# MODI3.net
KiCad netlist of a schematic drawn in EAGLE
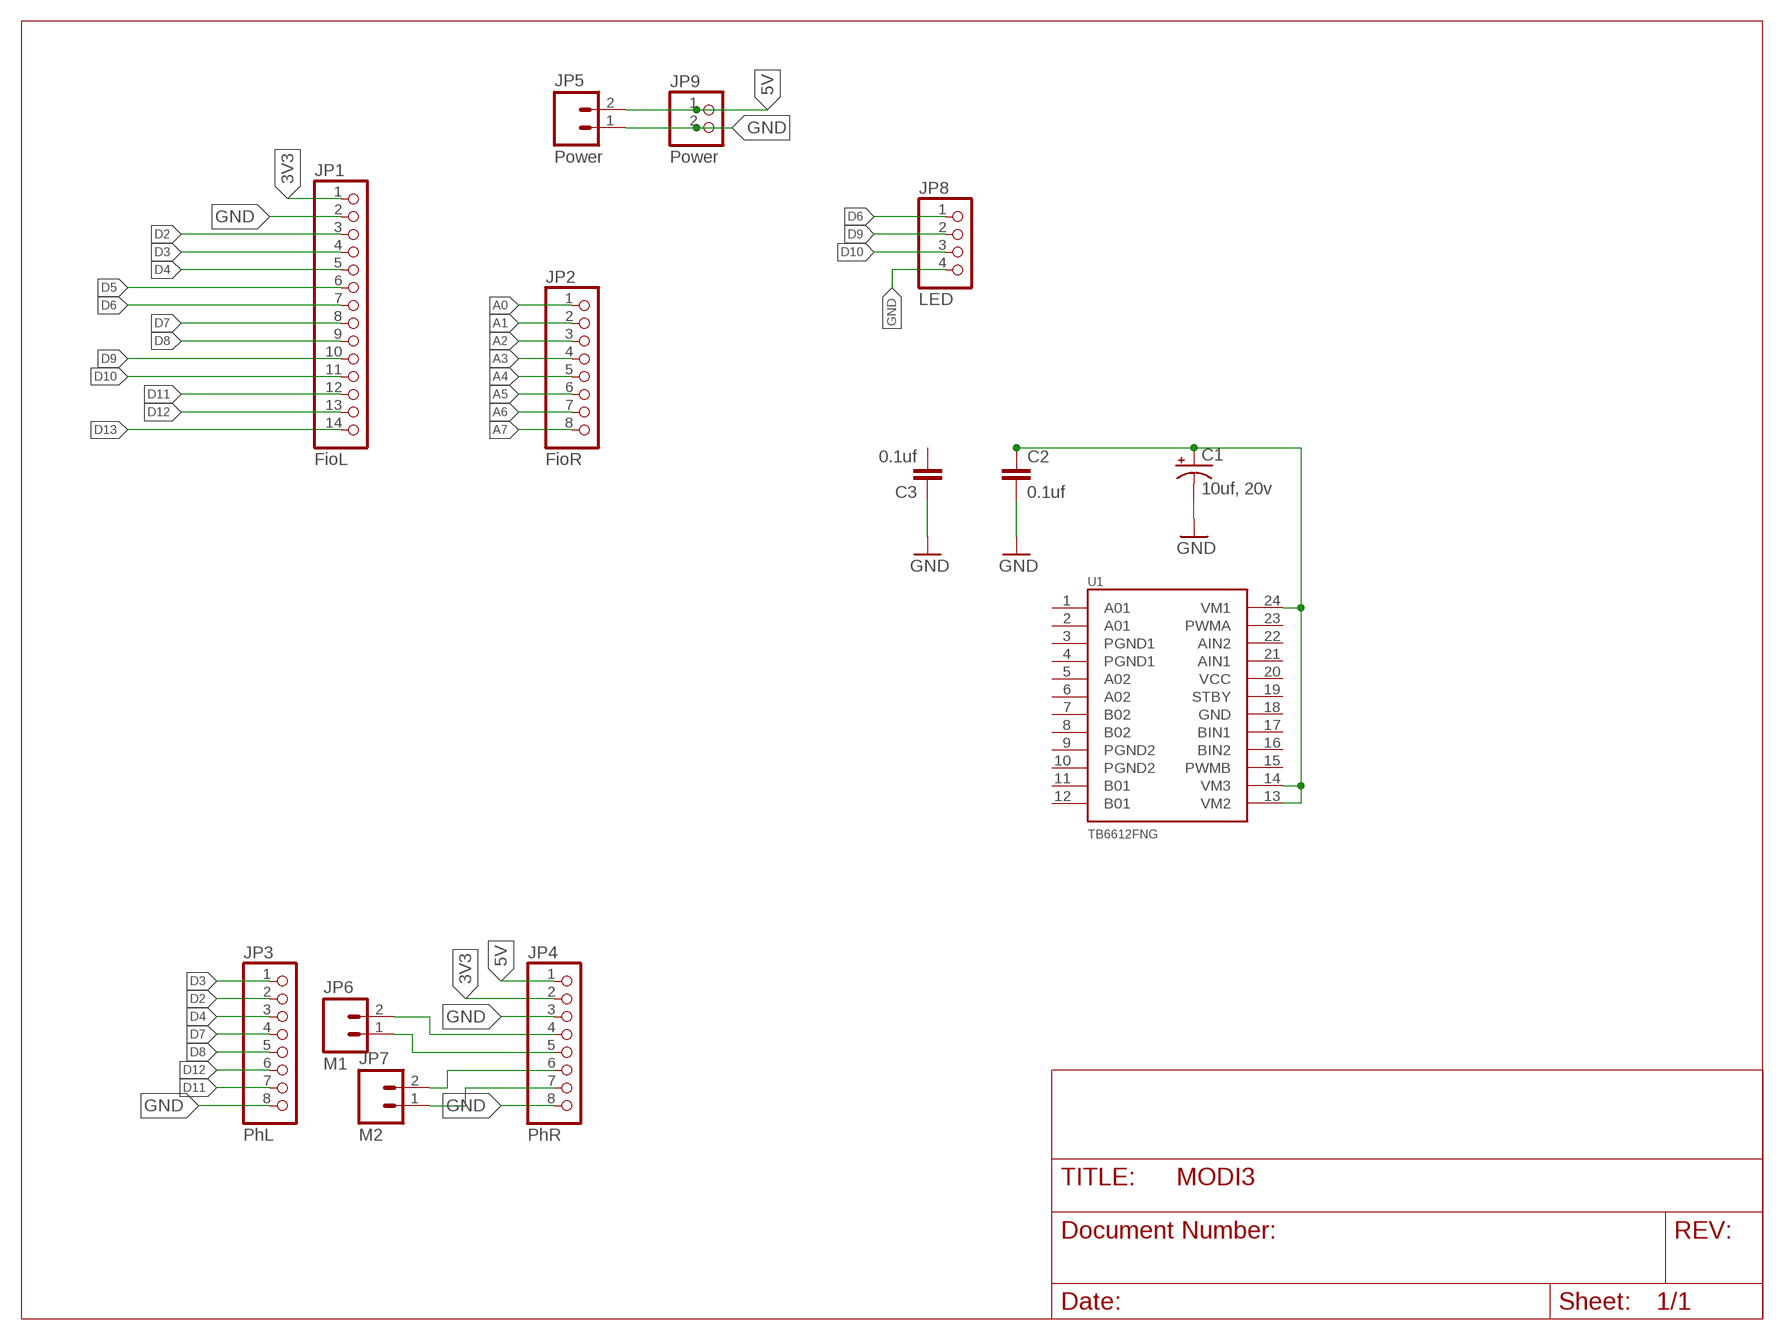
[diagram p0: schematic, sheet 1]

(export (version "E")
  (design (tool "Eeschema 10.0.6"))
  (components
    (comp (ref "C1")
      (value "10uf, 20v")
      (footprint "eagle-import:EIA3528")
      (libsource (lib "eagle-import") (part "CAP_POL3528"))
    )
    (comp (ref "C2")
      (value "0.1uf")
      (footprint "eagle-import:0402-CAP")
      (libsource (lib "eagle-import") (part "CAP0402-CAP"))
    )
    (comp (ref "C3")
      (value "0.1uf")
      (footprint "eagle-import:0402-CAP")
      (libsource (lib "eagle-import") (part "CAP0402-CAP"))
    )
    (comp (ref "JP1")
      (value "FioL")
      (footprint "eagle-import:1X14")
      (libsource (lib "eagle-import") (part "PINHD-1X14"))
    )
    (comp (ref "JP2")
      (value "FioR")
      (footprint "eagle-import:1X08")
      (libsource (lib "eagle-import") (part "PINHD-1X8"))
    )
    (comp (ref "JP3")
      (value "PhL")
      (footprint "eagle-import:1X08")
      (libsource (lib "eagle-import") (part "PINHD-1X8"))
    )
    (comp (ref "JP4")
      (value "PhR")
      (footprint "eagle-import:1X08")
      (libsource (lib "eagle-import") (part "PINHD-1X8"))
    )
    (comp (ref "JP5")
      (value "Power")
      (footprint "eagle-import:SCREWTERMINAL-3.5MM-2")
      (libsource (lib "eagle-import") (part "M023.5MM"))
    )
    (comp (ref "JP6")
      (value "M1")
      (footprint "eagle-import:SCREWTERMINAL-3.5MM-2")
      (libsource (lib "eagle-import") (part "M023.5MM"))
    )
    (comp (ref "JP7")
      (value "M2")
      (footprint "eagle-import:SCREWTERMINAL-3.5MM-2")
      (libsource (lib "eagle-import") (part "M023.5MM"))
    )
    (comp (ref "JP8")
      (value "LED")
      (footprint "eagle-import:1X04")
      (libsource (lib "eagle-import") (part "PINHD-1X4"))
    )
    (comp (ref "JP9")
      (value "Power")
      (footprint "eagle-import:1X02")
      (libsource (lib "eagle-import") (part "PINHD-1X2"))
    )
    (comp (ref "U1")
      (value "TB6612FNG")
      (footprint "eagle-import:SSOP24")
      (libsource (lib "eagle-import") (part "TB6621FNG"))
    )
  )
  (nets
    (net (code "1") (name "3V3") (class "Default")
      (node (ref "JP1") (pin "1") (pinfunction "1_1") (pintype "passive"))
      (node (ref "JP4") (pin "2") (pinfunction "2_2") (pintype "passive"))
    )
    (net (code "2") (name "5V") (class "Default")
      (node (ref "JP4") (pin "1") (pinfunction "1_1") (pintype "passive"))
      (node (ref "JP5") (pin "2") (pinfunction "2_2") (pintype "passive"))
      (node (ref "JP9") (pin "1") (pinfunction "1_1") (pintype "passive"))
    )
    (net (code "3") (name "A0") (class "Default")
      (node (ref "JP2") (pin "1") (pinfunction "1_1") (pintype "passive"))
    )
    (net (code "4") (name "A1") (class "Default")
      (node (ref "JP2") (pin "2") (pinfunction "2_2") (pintype "passive"))
    )
    (net (code "5") (name "A2") (class "Default")
      (node (ref "JP2") (pin "3") (pinfunction "3_3") (pintype "passive"))
    )
    (net (code "6") (name "A3") (class "Default")
      (node (ref "JP2") (pin "4") (pinfunction "4_4") (pintype "passive"))
    )
    (net (code "7") (name "A4") (class "Default")
      (node (ref "JP2") (pin "5") (pinfunction "5_5") (pintype "passive"))
    )
    (net (code "8") (name "A5") (class "Default")
      (node (ref "JP2") (pin "6") (pinfunction "6_6") (pintype "passive"))
    )
    (net (code "9") (name "A6") (class "Default")
      (node (ref "JP2") (pin "7") (pinfunction "7_7") (pintype "passive"))
    )
    (net (code "10") (name "A7") (class "Default")
      (node (ref "JP2") (pin "8") (pinfunction "8_8") (pintype "passive"))
    )
    (net (code "11") (name "D2") (class "Default")
      (node (ref "JP1") (pin "3") (pinfunction "3_3") (pintype "passive"))
      (node (ref "JP3") (pin "2") (pinfunction "2_2") (pintype "passive"))
    )
    (net (code "12") (name "D3") (class "Default")
      (node (ref "JP1") (pin "4") (pinfunction "4_4") (pintype "passive"))
      (node (ref "JP3") (pin "1") (pinfunction "1_1") (pintype "passive"))
    )
    (net (code "13") (name "D4") (class "Default")
      (node (ref "JP1") (pin "5") (pinfunction "5_5") (pintype "passive"))
      (node (ref "JP3") (pin "3") (pinfunction "3_3") (pintype "passive"))
    )
    (net (code "14") (name "D5") (class "Default")
      (node (ref "JP1") (pin "6") (pinfunction "6_6") (pintype "passive"))
    )
    (net (code "15") (name "D6") (class "Default")
      (node (ref "JP1") (pin "7") (pinfunction "7_7") (pintype "passive"))
      (node (ref "JP8") (pin "1") (pinfunction "1_1") (pintype "passive"))
    )
    (net (code "16") (name "D7") (class "Default")
      (node (ref "JP1") (pin "8") (pinfunction "8_8") (pintype "passive"))
      (node (ref "JP3") (pin "4") (pinfunction "4_4") (pintype "passive"))
    )
    (net (code "17") (name "D8") (class "Default")
      (node (ref "JP1") (pin "9") (pinfunction "9_9") (pintype "passive"))
      (node (ref "JP3") (pin "5") (pinfunction "5_5") (pintype "passive"))
    )
    (net (code "18") (name "D9") (class "Default")
      (node (ref "JP1") (pin "10") (pinfunction "10_10") (pintype "passive"))
      (node (ref "JP8") (pin "2") (pinfunction "2_2") (pintype "passive"))
    )
    (net (code "19") (name "D10") (class "Default")
      (node (ref "JP1") (pin "11") (pinfunction "11_11") (pintype "passive"))
      (node (ref "JP8") (pin "3") (pinfunction "3_3") (pintype "passive"))
    )
    (net (code "20") (name "D11") (class "Default")
      (node (ref "JP1") (pin "12") (pinfunction "12_12") (pintype "passive"))
      (node (ref "JP3") (pin "7") (pinfunction "7_7") (pintype "passive"))
    )
    (net (code "21") (name "D12") (class "Default")
      (node (ref "JP1") (pin "13") (pinfunction "13_13") (pintype "passive"))
      (node (ref "JP3") (pin "6") (pinfunction "6_6") (pintype "passive"))
    )
    (net (code "22") (name "D13") (class "Default")
      (node (ref "JP1") (pin "14") (pinfunction "14_14") (pintype "passive"))
    )
    (net (code "23") (name "GND") (class "Default")
      (node (ref "C1") (pin "C") (pinfunction "-_C") (pintype "passive"))
      (node (ref "C2") (pin "2") (pinfunction "2_2") (pintype "passive"))
      (node (ref "C3") (pin "1") (pinfunction "1_1") (pintype "passive"))
      (node (ref "JP1") (pin "2") (pinfunction "2_2") (pintype "passive"))
      (node (ref "JP3") (pin "8") (pinfunction "8_8") (pintype "passive"))
      (node (ref "JP4") (pin "3") (pinfunction "3_3") (pintype "passive"))
      (node (ref "JP4") (pin "8") (pinfunction "8_8") (pintype "passive"))
      (node (ref "JP5") (pin "1") (pinfunction "1_1") (pintype "passive"))
      (node (ref "JP8") (pin "4") (pinfunction "4_4") (pintype "passive"))
      (node (ref "JP9") (pin "2") (pinfunction "2_2") (pintype "passive"))
    )
    (net (code "24") (name "Net-(C1-+)") (class "Default")
      (node (ref "C1") (pin "A") (pinfunction "+_A") (pintype "passive"))
      (node (ref "C2") (pin "1") (pinfunction "1_1") (pintype "passive"))
      (node (ref "U1") (pin "13") (pinfunction "VM2_13") (pintype "bidirectional"))
      (node (ref "U1") (pin "14") (pinfunction "VM3_14") (pintype "bidirectional"))
      (node (ref "U1") (pin "24") (pinfunction "VM1_24") (pintype "bidirectional"))
    )
    (net (code "25") (name "Net-(JP4-Pad4)") (class "Default")
      (node (ref "JP4") (pin "4") (pinfunction "4_4") (pintype "passive"))
      (node (ref "JP6") (pin "2") (pinfunction "2_2") (pintype "passive"))
    )
    (net (code "26") (name "Net-(JP4-Pad5)") (class "Default")
      (node (ref "JP4") (pin "5") (pinfunction "5_5") (pintype "passive"))
      (node (ref "JP6") (pin "1") (pinfunction "1_1") (pintype "passive"))
    )
    (net (code "27") (name "Net-(JP4-Pad6)") (class "Default")
      (node (ref "JP4") (pin "6") (pinfunction "6_6") (pintype "passive"))
      (node (ref "JP7") (pin "2") (pinfunction "2_2") (pintype "passive"))
    )
    (net (code "28") (name "Net-(JP4-Pad7)") (class "Default")
      (node (ref "JP4") (pin "7") (pinfunction "7_7") (pintype "passive"))
      (node (ref "JP7") (pin "1") (pinfunction "1_1") (pintype "passive"))
    )
    (net (code "29") (name "unconnected-(C3-Pad2)") (class "Default")
      (node (ref "C3") (pin "2") (pinfunction "2_2") (pintype "passive"))
    )
    (net (code "30") (name "unconnected-(U1-A01-Pad1)") (class "Default")
      (node (ref "U1") (pin "1") (pinfunction "A01_1") (pintype "bidirectional"))
    )
    (net (code "31") (name "unconnected-(U1-A01-Pad2)") (class "Default")
      (node (ref "U1") (pin "2") (pinfunction "A01_2") (pintype "bidirectional"))
    )
    (net (code "32") (name "unconnected-(U1-A02-Pad5)") (class "Default")
      (node (ref "U1") (pin "5") (pinfunction "A02_5") (pintype "bidirectional"))
    )
    (net (code "33") (name "unconnected-(U1-A02-Pad6)") (class "Default")
      (node (ref "U1") (pin "6") (pinfunction "A02_6") (pintype "bidirectional"))
    )
    (net (code "34") (name "unconnected-(U1-AIN1-Pad21)") (class "Default")
      (node (ref "U1") (pin "21") (pinfunction "AIN1_21") (pintype "bidirectional"))
    )
    (net (code "35") (name "unconnected-(U1-AIN2-Pad22)") (class "Default")
      (node (ref "U1") (pin "22") (pinfunction "AIN2_22") (pintype "bidirectional"))
    )
    (net (code "36") (name "unconnected-(U1-B01-Pad11)") (class "Default")
      (node (ref "U1") (pin "11") (pinfunction "B01_11") (pintype "bidirectional"))
    )
    (net (code "37") (name "unconnected-(U1-B01-Pad12)") (class "Default")
      (node (ref "U1") (pin "12") (pinfunction "B01_12") (pintype "bidirectional"))
    )
    (net (code "38") (name "unconnected-(U1-B02-Pad7)") (class "Default")
      (node (ref "U1") (pin "7") (pinfunction "B02_7") (pintype "bidirectional"))
    )
    (net (code "39") (name "unconnected-(U1-B02-Pad8)") (class "Default")
      (node (ref "U1") (pin "8") (pinfunction "B02_8") (pintype "bidirectional"))
    )
    (net (code "40") (name "unconnected-(U1-BIN1-Pad17)") (class "Default")
      (node (ref "U1") (pin "17") (pinfunction "BIN1_17") (pintype "bidirectional"))
    )
    (net (code "41") (name "unconnected-(U1-BIN2-Pad16)") (class "Default")
      (node (ref "U1") (pin "16") (pinfunction "BIN2_16") (pintype "bidirectional"))
    )
    (net (code "42") (name "unconnected-(U1-GND-Pad18)") (class "Default")
      (node (ref "U1") (pin "18") (pinfunction "GND_18") (pintype "bidirectional"))
    )
    (net (code "43") (name "unconnected-(U1-PGND1-Pad3)") (class "Default")
      (node (ref "U1") (pin "3") (pinfunction "PGND1_3") (pintype "bidirectional"))
    )
    (net (code "44") (name "unconnected-(U1-PGND1-Pad4)") (class "Default")
      (node (ref "U1") (pin "4") (pinfunction "PGND1_4") (pintype "bidirectional"))
    )
    (net (code "45") (name "unconnected-(U1-PGND2-Pad9)") (class "Default")
      (node (ref "U1") (pin "9") (pinfunction "PGND2_9") (pintype "bidirectional"))
    )
    (net (code "46") (name "unconnected-(U1-PGND2-Pad10)") (class "Default")
      (node (ref "U1") (pin "10") (pinfunction "PGND2_10") (pintype "bidirectional"))
    )
    (net (code "47") (name "unconnected-(U1-PWMA-Pad23)") (class "Default")
      (node (ref "U1") (pin "23") (pinfunction "PWMA_23") (pintype "bidirectional"))
    )
    (net (code "48") (name "unconnected-(U1-PWMB-Pad15)") (class "Default")
      (node (ref "U1") (pin "15") (pinfunction "PWMB_15") (pintype "bidirectional"))
    )
    (net (code "49") (name "unconnected-(U1-STBY-Pad19)") (class "Default")
      (node (ref "U1") (pin "19") (pinfunction "STBY_19") (pintype "bidirectional"))
    )
    (net (code "50") (name "unconnected-(U1-VCC-Pad20)") (class "Default")
      (node (ref "U1") (pin "20") (pinfunction "VCC_20") (pintype "bidirectional"))
    )
  )
)
